# path_panel.net
KiCad netlist of a schematic drawn in EAGLE
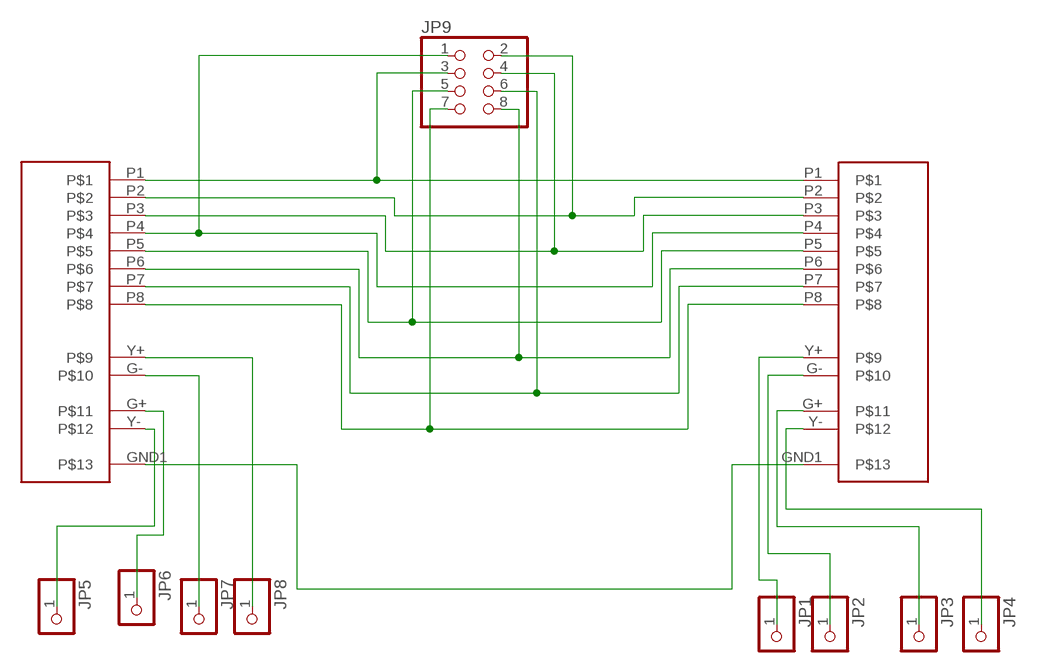
[diagram p0: schematic, sheet 1]

(export (version "E")
  (design (tool "Eeschema 10.0.6"))
  (components
    (comp (ref "JP1")
      (value "PINHD-1X1")
      (footprint "eagle-import:1X01")
      (libsource (lib "eagle-import") (part "PINHD-1X1"))
    )
    (comp (ref "JP2")
      (value "PINHD-1X1")
      (footprint "eagle-import:1X01")
      (libsource (lib "eagle-import") (part "PINHD-1X1"))
    )
    (comp (ref "JP3")
      (value "PINHD-1X1")
      (footprint "eagle-import:1X01")
      (libsource (lib "eagle-import") (part "PINHD-1X1"))
    )
    (comp (ref "JP4")
      (value "PINHD-1X1")
      (footprint "eagle-import:1X01")
      (libsource (lib "eagle-import") (part "PINHD-1X1"))
    )
    (comp (ref "JP5")
      (value "PINHD-1X1")
      (footprint "eagle-import:1X01")
      (libsource (lib "eagle-import") (part "PINHD-1X1"))
    )
    (comp (ref "JP6")
      (value "PINHD-1X1")
      (footprint "eagle-import:1X01")
      (libsource (lib "eagle-import") (part "PINHD-1X1"))
    )
    (comp (ref "JP7")
      (value "PINHD-1X1")
      (footprint "eagle-import:1X01")
      (libsource (lib "eagle-import") (part "PINHD-1X1"))
    )
    (comp (ref "JP8")
      (value "PINHD-1X1")
      (footprint "eagle-import:1X01")
      (libsource (lib "eagle-import") (part "PINHD-1X1"))
    )
    (comp (ref "JP9")
      (value "PINHD-2X4")
      (footprint "eagle-import:2X04")
      (libsource (lib "eagle-import") (part "PINHD-2X4"))
    )
    (comp (ref "U$14")
      (value "RJ-45_LEDS")
      (footprint "eagle-import:RJ-45_LEDS")
      (libsource (lib "eagle-import") (part "RJ-45_LEDS"))
    )
    (comp (ref "U$15")
      (value "RJ-45_LEDS")
      (footprint "eagle-import:RJ-45_LEDS")
      (libsource (lib "eagle-import") (part "RJ-45_LEDS"))
    )
  )
  (nets
    (net (code "1") (name "Net-(U$14-P$1)") (class "Default")
      (node (ref "JP9") (pin "3") (pinfunction "3_3") (pintype "passive"))
      (node (ref "U$14") (pin "P1") (pinfunction "P$1_P1") (pintype "bidirectional"))
      (node (ref "U$15") (pin "P1") (pinfunction "P$1_P1") (pintype "bidirectional"))
    )
    (net (code "2") (name "Net-(U$14-P$2)") (class "Default")
      (node (ref "JP9") (pin "2") (pinfunction "2_2") (pintype "passive"))
      (node (ref "U$14") (pin "P2") (pinfunction "P$2_P2") (pintype "bidirectional"))
      (node (ref "U$15") (pin "P2") (pinfunction "P$2_P2") (pintype "bidirectional"))
    )
    (net (code "3") (name "Net-(U$14-P$3)") (class "Default")
      (node (ref "JP9") (pin "4") (pinfunction "4_4") (pintype "passive"))
      (node (ref "U$14") (pin "P3") (pinfunction "P$3_P3") (pintype "bidirectional"))
      (node (ref "U$15") (pin "P3") (pinfunction "P$3_P3") (pintype "bidirectional"))
    )
    (net (code "4") (name "Net-(U$14-P$4)") (class "Default")
      (node (ref "JP9") (pin "1") (pinfunction "1_1") (pintype "passive"))
      (node (ref "U$14") (pin "P4") (pinfunction "P$4_P4") (pintype "bidirectional"))
      (node (ref "U$15") (pin "P4") (pinfunction "P$4_P4") (pintype "bidirectional"))
    )
    (net (code "5") (name "Net-(U$14-P$5)") (class "Default")
      (node (ref "JP9") (pin "5") (pinfunction "5_5") (pintype "passive"))
      (node (ref "U$14") (pin "P5") (pinfunction "P$5_P5") (pintype "bidirectional"))
      (node (ref "U$15") (pin "P5") (pinfunction "P$5_P5") (pintype "bidirectional"))
    )
    (net (code "6") (name "Net-(U$14-P$6)") (class "Default")
      (node (ref "JP9") (pin "8") (pinfunction "8_8") (pintype "passive"))
      (node (ref "U$14") (pin "P6") (pinfunction "P$6_P6") (pintype "bidirectional"))
      (node (ref "U$15") (pin "P6") (pinfunction "P$6_P6") (pintype "bidirectional"))
    )
    (net (code "7") (name "Net-(U$14-P$7)") (class "Default")
      (node (ref "JP9") (pin "6") (pinfunction "6_6") (pintype "passive"))
      (node (ref "U$14") (pin "P7") (pinfunction "P$7_P7") (pintype "bidirectional"))
      (node (ref "U$15") (pin "P7") (pinfunction "P$7_P7") (pintype "bidirectional"))
    )
    (net (code "8") (name "Net-(U$14-P$8)") (class "Default")
      (node (ref "JP9") (pin "7") (pinfunction "7_7") (pintype "passive"))
      (node (ref "U$14") (pin "P8") (pinfunction "P$8_P8") (pintype "bidirectional"))
      (node (ref "U$15") (pin "P8") (pinfunction "P$8_P8") (pintype "bidirectional"))
    )
    (net (code "9") (name "Net-(U$14-P$9)") (class "Default")
      (node (ref "JP8") (pin "1") (pinfunction "1_1") (pintype "passive"))
      (node (ref "U$14") (pin "Y+") (pinfunction "P$9_Y+") (pintype "power_in"))
    )
    (net (code "10") (name "Net-(U$14-P$10)") (class "Default")
      (node (ref "JP7") (pin "1") (pinfunction "1_1") (pintype "passive"))
      (node (ref "U$14") (pin "G-") (pinfunction "P$10_G-") (pintype "power_in"))
    )
    (net (code "11") (name "Net-(U$14-P$11)") (class "Default")
      (node (ref "JP6") (pin "1") (pinfunction "1_1") (pintype "passive"))
      (node (ref "U$14") (pin "G+") (pinfunction "P$11_G+") (pintype "power_in"))
    )
    (net (code "12") (name "Net-(U$14-P$12)") (class "Default")
      (node (ref "JP5") (pin "1") (pinfunction "1_1") (pintype "passive"))
      (node (ref "U$14") (pin "Y-") (pinfunction "P$12_Y-") (pintype "power_in"))
    )
    (net (code "13") (name "Net-(U$14-P$13)") (class "Default")
      (node (ref "U$14") (pin "GND1") (pinfunction "P$13_GND1") (pintype "power_in"))
      (node (ref "U$15") (pin "GND1") (pinfunction "P$13_GND1") (pintype "power_in"))
    )
    (net (code "14") (name "Net-(U$15-P$9)") (class "Default")
      (node (ref "JP1") (pin "1") (pinfunction "1_1") (pintype "passive"))
      (node (ref "U$15") (pin "Y+") (pinfunction "P$9_Y+") (pintype "power_in"))
    )
    (net (code "15") (name "Net-(U$15-P$10)") (class "Default")
      (node (ref "JP2") (pin "1") (pinfunction "1_1") (pintype "passive"))
      (node (ref "U$15") (pin "G-") (pinfunction "P$10_G-") (pintype "power_in"))
    )
    (net (code "16") (name "Net-(U$15-P$11)") (class "Default")
      (node (ref "JP3") (pin "1") (pinfunction "1_1") (pintype "passive"))
      (node (ref "U$15") (pin "G+") (pinfunction "P$11_G+") (pintype "power_in"))
    )
    (net (code "17") (name "Net-(U$15-P$12)") (class "Default")
      (node (ref "JP4") (pin "1") (pinfunction "1_1") (pintype "passive"))
      (node (ref "U$15") (pin "Y-") (pinfunction "P$12_Y-") (pintype "power_in"))
    )
  )
)
